# 7_DAC_and_MIC.net
KiCad netlist of a schematic drawn in Altium Designer
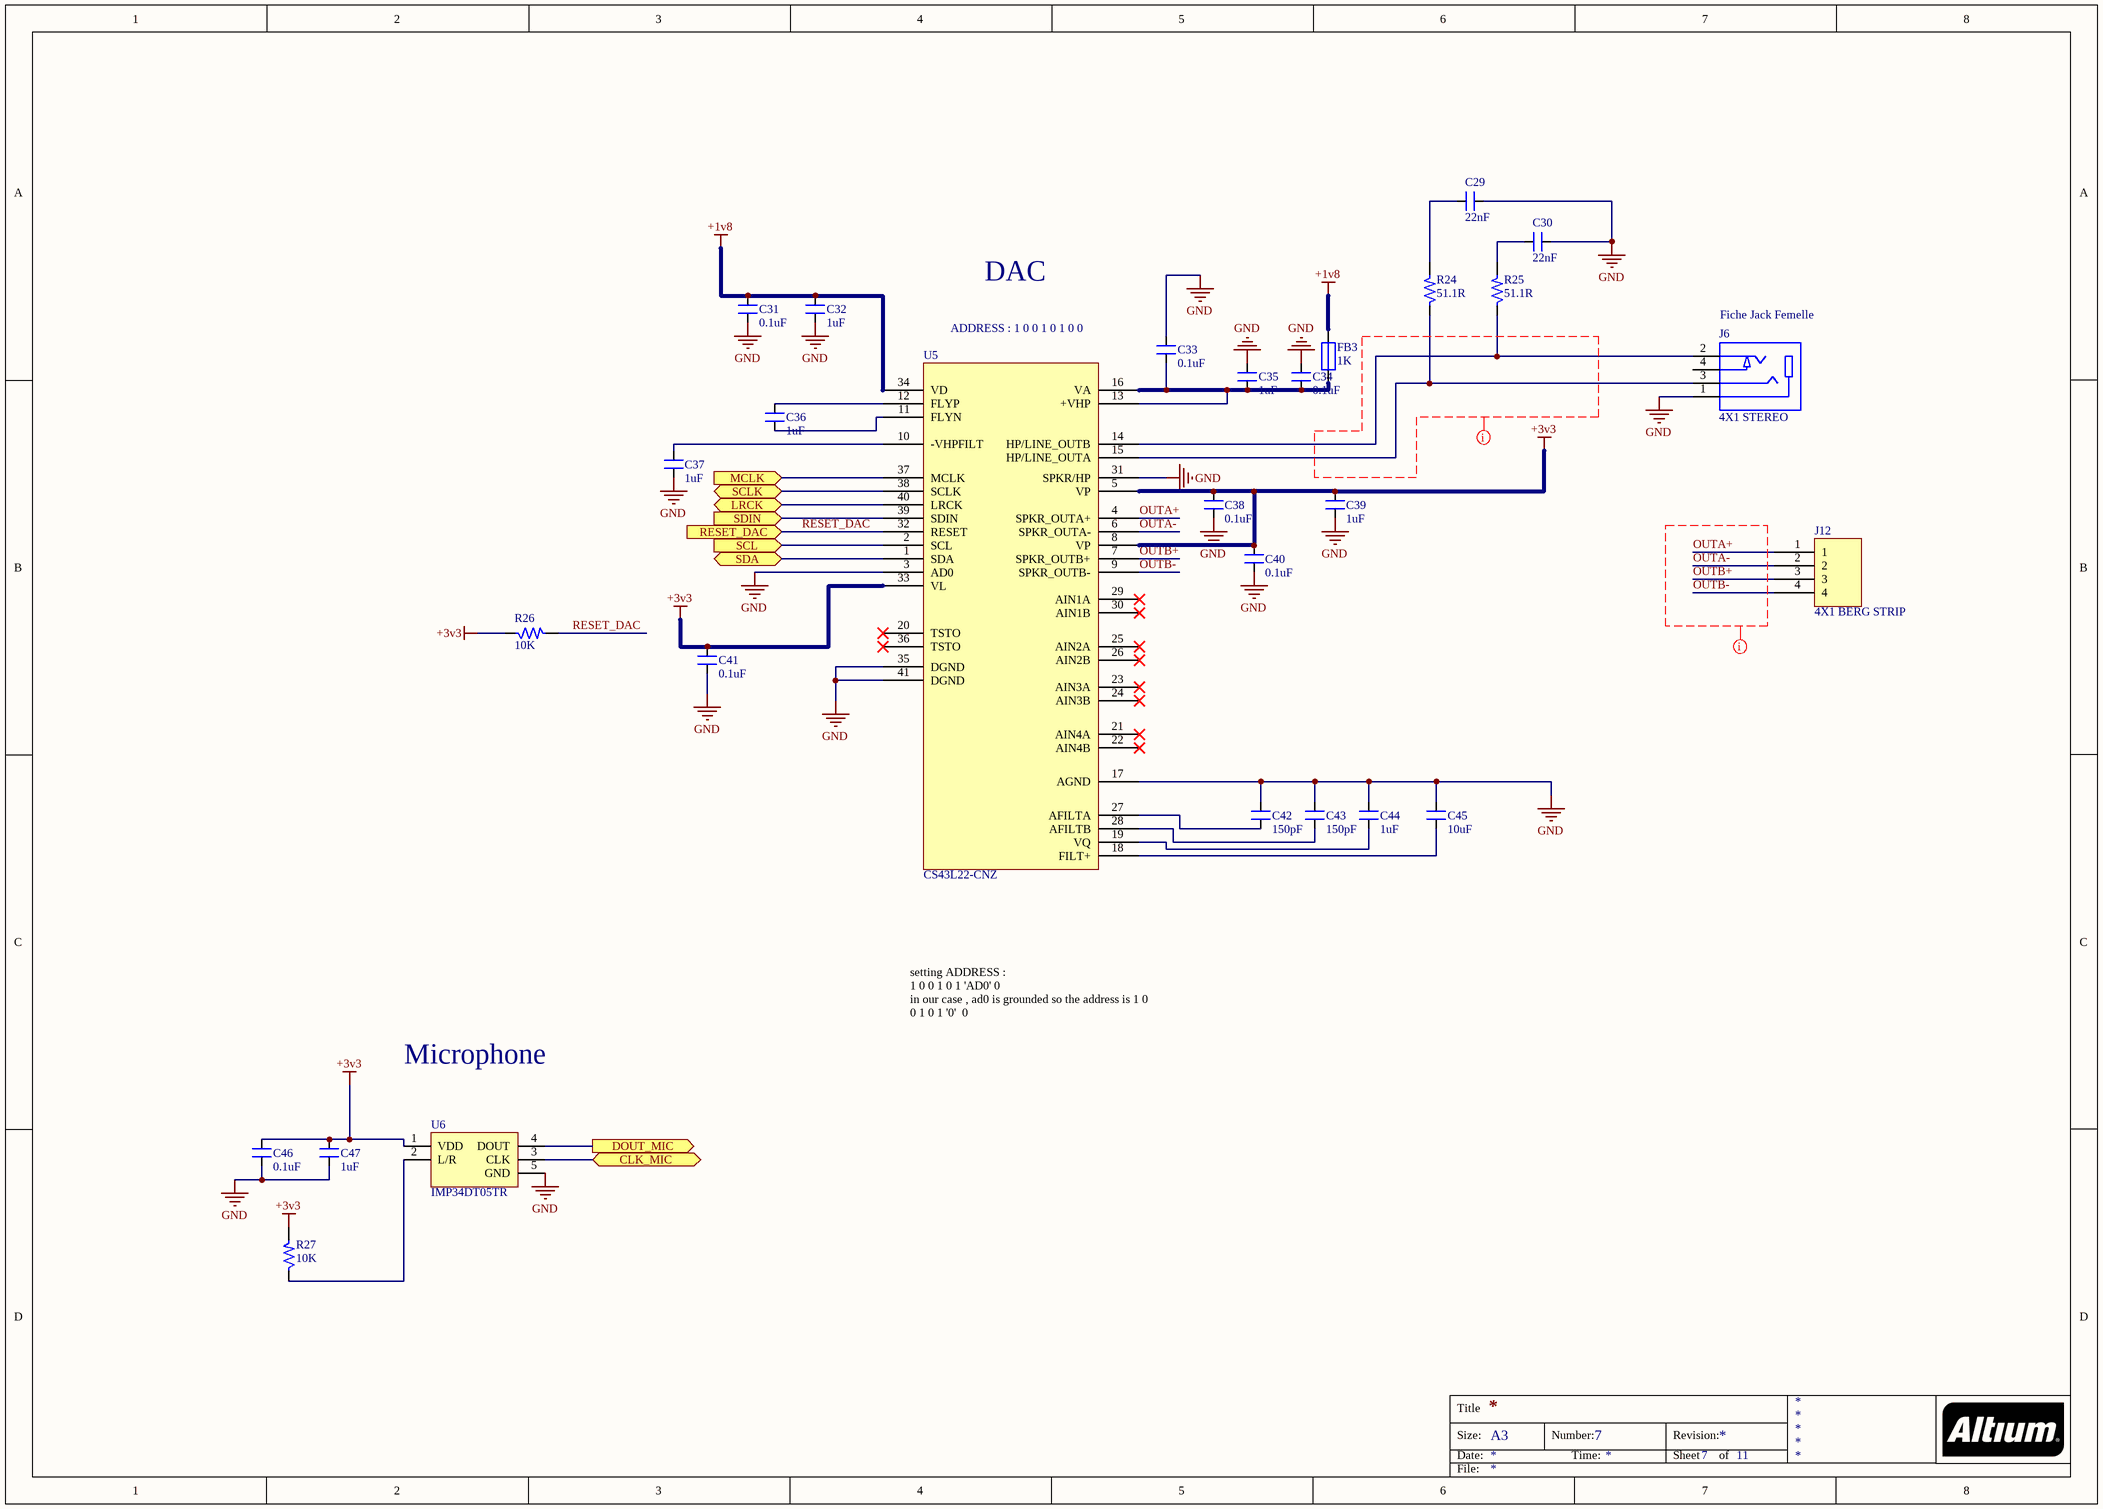
[diagram p0: [7]DAC_and_MIC.SchDoc]

(export (version "E")
  (design (tool "Eeschema 10.0.6"))
  (components
    (comp (ref "C29")
      (value "22nF")
      (footprint "CAP_0805")
      (description "0.022µF ±10% 50V Ceramic Capacitor X7R 0805 (2012 Metric)")
      (fields
        (field (name "MANUFACTURER") "Samsung Electro-Mechanics")
        (field (name "MANUFACTURER PART NUMBER") "CL21B223KBANNNC")
      )
      (libsource (lib "ESTEEMPCBLIB") (part "CAP_22nF-50V-10%-0805"))
    )
    (comp (ref "C30")
      (value "22nF")
      (footprint "CAP_0805")
      (description "0.022µF ±10% 50V Ceramic Capacitor X7R 0805 (2012 Metric)")
      (fields
        (field (name "MANUFACTURER") "Samsung Electro-Mechanics")
        (field (name "MANUFACTURER PART NUMBER") "CL21B223KBANNNC")
      )
      (libsource (lib "ESTEEMPCBLIB") (part "CAP_22nF-50V-10%-0805"))
    )
    (comp (ref "C31")
      (value "0.1uF")
      (footprint "CAP_0805")
      (description "0.1µF ±5% 50V Ceramic Capacitor X7R 0805 (2012 Metric)")
      (fields
        (field (name "MANUFACTURER") "AVX Corporation")
        (field (name "MANUFACTURER PART NUMBER") "08055C104JAT4A")
      )
      (libsource (lib "ESTEEMPCBLIB") (part "CAP_0.1uF-50V-5%-0805"))
    )
    (comp (ref "C32")
      (value "1uF")
      (footprint "CAP_0805")
      (description "1µF ±5% 50V Ceramic Capacitor X7R 0805 (2012 Metric)")
      (fields
        (field (name "MANUFACTURER") "Samsung")
        (field (name "MANUFACTURER PART NUMBER") "CC0805JKX7R9BB105")
      )
      (libsource (lib "ESTEEMPCBLIB") (part "CAP_1uF-50V-5%-0805"))
    )
    (comp (ref "C33")
      (value "0.1uF")
      (footprint "CAP_0805")
      (description "0.1µF ±5% 50V Ceramic Capacitor X7R 0805 (2012 Metric)")
      (fields
        (field (name "MANUFACTURER") "AVX Corporation")
        (field (name "MANUFACTURER PART NUMBER") "08055C104JAT4A")
      )
      (libsource (lib "ESTEEMPCBLIB") (part "CAP_0.1uF-50V-5%-0805"))
    )
    (comp (ref "C34")
      (value "0.1uF")
      (footprint "CAP_0805")
      (description "0.1µF ±5% 50V Ceramic Capacitor X7R 0805 (2012 Metric)")
      (fields
        (field (name "MANUFACTURER") "AVX Corporation")
        (field (name "MANUFACTURER PART NUMBER") "08055C104JAT4A")
      )
      (libsource (lib "ESTEEMPCBLIB") (part "CAP_0.1uF-50V-5%-0805"))
    )
    (comp (ref "C35")
      (value "1uF")
      (footprint "CAP_0805")
      (description "1µF ±5% 50V Ceramic Capacitor X7R 0805 (2012 Metric)")
      (fields
        (field (name "MANUFACTURER") "Samsung")
        (field (name "MANUFACTURER PART NUMBER") "CC0805JKX7R9BB105")
      )
      (libsource (lib "ESTEEMPCBLIB") (part "CAP_1uF-50V-5%-0805"))
    )
    (comp (ref "C36")
      (value "1uF")
      (footprint "CAP_0805")
      (description "1µF ±5% 50V Ceramic Capacitor X7R 0805 (2012 Metric)")
      (fields
        (field (name "MANUFACTURER") "Samsung")
        (field (name "MANUFACTURER PART NUMBER") "CC0805JKX7R9BB105")
      )
      (libsource (lib "ESTEEMPCBLIB") (part "CAP_1uF-50V-5%-0805"))
    )
    (comp (ref "C37")
      (value "1uF")
      (footprint "CAP_0805")
      (description "1µF ±5% 50V Ceramic Capacitor X7R 0805 (2012 Metric)")
      (fields
        (field (name "MANUFACTURER") "Samsung")
        (field (name "MANUFACTURER PART NUMBER") "CC0805JKX7R9BB105")
      )
      (libsource (lib "ESTEEMPCBLIB") (part "CAP_1uF-50V-5%-0805"))
    )
    (comp (ref "C38")
      (value "0.1uF")
      (footprint "CAP_0805")
      (description "0.1µF ±5% 50V Ceramic Capacitor X7R 0805 (2012 Metric)")
      (fields
        (field (name "MANUFACTURER") "AVX Corporation")
        (field (name "MANUFACTURER PART NUMBER") "08055C104JAT4A")
      )
      (libsource (lib "ESTEEMPCBLIB") (part "CAP_0.1uF-50V-5%-0805"))
    )
    (comp (ref "C39")
      (value "1uF")
      (footprint "CAP_0805")
      (description "1µF ±5% 50V Ceramic Capacitor X7R 0805 (2012 Metric)")
      (fields
        (field (name "MANUFACTURER") "Samsung")
        (field (name "MANUFACTURER PART NUMBER") "CC0805JKX7R9BB105")
      )
      (libsource (lib "ESTEEMPCBLIB") (part "CAP_1uF-50V-5%-0805"))
    )
    (comp (ref "C40")
      (value "0.1uF")
      (footprint "CAP_0805")
      (description "0.1µF ±5% 50V Ceramic Capacitor X7R 0805 (2012 Metric)")
      (fields
        (field (name "MANUFACTURER") "AVX Corporation")
        (field (name "MANUFACTURER PART NUMBER") "08055C104JAT4A")
      )
      (libsource (lib "ESTEEMPCBLIB") (part "CAP_0.1uF-50V-5%-0805"))
    )
    (comp (ref "C41")
      (value "0.1uF")
      (footprint "CAP_0805")
      (description "0.1µF ±5% 50V Ceramic Capacitor X7R 0805 (2012 Metric)")
      (fields
        (field (name "MANUFACTURER") "AVX Corporation")
        (field (name "MANUFACTURER PART NUMBER") "08055C104JAT4A")
      )
      (libsource (lib "ESTEEMPCBLIB") (part "CAP_0.1uF-50V-5%-0805"))
    )
    (comp (ref "C42")
      (value "150pF")
      (footprint "CAP_0805")
      (description "150pF ±10% 50V Ceramic Capacitor C0G, NP0 0805 (2012 Metric)")
      (fields
        (field (name "MANUFACTURER") "AVX Corporation")
        (field (name "MANUFACTURER PART NUMBER") "08055A151KAT2A")
      )
      (libsource (lib "ESTEEMPCBLIB") (part "CAP_150pF-50V-10%-0805"))
    )
    (comp (ref "C43")
      (value "150pF")
      (footprint "CAP_0805")
      (description "150pF ±10% 50V Ceramic Capacitor C0G, NP0 0805 (2012 Metric)")
      (fields
        (field (name "MANUFACTURER") "AVX Corporation")
        (field (name "MANUFACTURER PART NUMBER") "08055A151KAT2A")
      )
      (libsource (lib "ESTEEMPCBLIB") (part "CAP_150pF-50V-10%-0805"))
    )
    (comp (ref "C44")
      (value "1uF")
      (footprint "CAP_0805")
      (description "1µF ±5% 50V Ceramic Capacitor X7R 0805 (2012 Metric)")
      (fields
        (field (name "MANUFACTURER") "Samsung")
        (field (name "MANUFACTURER PART NUMBER") "CC0805JKX7R9BB105")
      )
      (libsource (lib "ESTEEMPCBLIB") (part "CAP_1uF-50V-5%-0805"))
    )
    (comp (ref "C45")
      (value "10uF")
      (footprint "CAP_1206")
      (description "10µF ±10% 50V Ceramic Capacitor X7R 1206 (3216 Metric)")
      (fields
        (field (name "MANUFACTURER") "KEMET")
        (field (name "MANUFACTURER PART NUMBER") "CL31B106KBHNNNE")
      )
      (libsource (lib "ESTEEMPCBLIB") (part "CAP_10uF-50V-10%-1206"))
    )
    (comp (ref "C46")
      (value "0.1uF")
      (footprint "CAP_0805")
      (description "0.1µF ±5% 50V Ceramic Capacitor X7R 0805 (2012 Metric)")
      (fields
        (field (name "MANUFACTURER") "AVX Corporation")
        (field (name "MANUFACTURER PART NUMBER") "08055C104JAT4A")
      )
      (libsource (lib "ESTEEMPCBLIB") (part "CAP_0.1uF-50V-5%-0805"))
    )
    (comp (ref "C47")
      (value "1uF")
      (footprint "CAP_0805")
      (description "1µF ±5% 50V Ceramic Capacitor X7R 0805 (2012 Metric)")
      (fields
        (field (name "MANUFACTURER") "Samsung")
        (field (name "MANUFACTURER PART NUMBER") "CC0805JKX7R9BB105")
      )
      (libsource (lib "ESTEEMPCBLIB") (part "CAP_1uF-50V-5%-0805"))
    )
    (comp (ref "FB3")
      (value "1K")
      (footprint "IND_0805")
      (description "1 kOhms @ 100MHz 1 Power Line Ferrite Bead 0805 (2012 Metric) 1.6A")
      (fields
        (field (name "MANUFACTURER") "Laird")
        (field (name "MANUFACTURER PART NUMBER") "BLM21SP102SH1D")
      )
      (libsource (lib "ESTEEMPCBLIB") (part "FB_1K-100MHZ-1.6A-0805"))
    )
    (comp (ref "J6")
      (value "4X1 STEREO")
      (footprint "CON_SJ-2504A-SMT-TR_SMD")
      (fields
        (field (name "MANUFACTURER") "CUI Devices")
        (field (name "MANUFACTURER PART NUMBER") "SJ-2504A-SMT-TR")
      )
      (libsource (lib "ESTEEMPCBLIB") (part "CON-PLG-STEREO_4X1-100-RA-SMD"))
    )
    (comp (ref "J12")
      (value "4X1 BERG STRIP")
      (footprint "CON4_100_40D72_TH_ST_MALE")
      (description "4 Pins, 1 Row 2.54mm Pitch, Straight bergstrip, Male")
      (fields (field (name "MANUFACTURER") "NA"))
      (libsource (lib "ESTEEMPCBLIB") (part "CON-BS-PLG_4X1-100-ST-TH"))
    )
    (comp (ref "R24")
      (value "51.1R")
      (footprint "RES_0603")
      (description "51.1 Ohms ±1% 0.1W, 1/10W Chip Resistor 0603 (1608 Metric) Thick Film")
      (fields
        (field (name "MANUFACTURER") "Vishay Dale")
        (field (name "MANUFACTURER PART NUMBER") "CRCW060351R1FKEAC")
      )
      (libsource (lib "ESTEEMPCBLIB") (part "RES_51.1R-0.1W-1%-0603"))
    )
    (comp (ref "R25")
      (value "51.1R")
      (footprint "RES_0603")
      (description "51.1 Ohms ±1% 0.1W, 1/10W Chip Resistor 0603 (1608 Metric) Thick Film")
      (fields
        (field (name "MANUFACTURER") "Vishay Dale")
        (field (name "MANUFACTURER PART NUMBER") "CRCW060351R1FKEAC")
      )
      (libsource (lib "ESTEEMPCBLIB") (part "RES_51.1R-0.1W-1%-0603"))
    )
    (comp (ref "R26")
      (value "10K")
      (footprint "RES_0603")
      (description "10 kOhms ±1% 0.1W, 1/10W Chip Resistor 0603 (1608 Metric) Automotive AEC-Q200 Thick Film")
      (fields (field (name "MANUFACTURER") "Walsin") (field (name "MANUFACTURER PART NUMBER") "WR06X1002FTL"))
      (libsource (lib "ESTEEMPCBLIB") (part "RES_10K-0.1W-1%-0603"))
    )
    (comp (ref "R27")
      (value "10K")
      (footprint "RES_0603")
      (description "10 kOhms ±1% 0.1W, 1/10W Chip Resistor 0603 (1608 Metric) Automotive AEC-Q200 Thick Film")
      (fields (field (name "MANUFACTURER") "Walsin") (field (name "MANUFACTURER PART NUMBER") "WR06X1002FTL"))
      (libsource (lib "ESTEEMPCBLIB") (part "RES_10K-0.1W-1%-0603"))
    )
    (comp (ref "U5")
      (value "CS43L22-CNZ")
      (footprint "QFN40_19_284_33X9_SMD")
      (description "Audio D/A Converter ICs Low Power Stereo DAC w/ClassD Spkr Driver")
      (fields (field (name "MANUFACTURER") "Cirrus Logic"))
      (libsource (lib "ESTEEMPCBLIB") (part "IC_CS43L22"))
    )
    (comp (ref "U6")
      (value "IMP34DT05TR")
      (footprint "HCLGA-4_53_137_15X37_SMD")
      (description "MEMS Microphones AUTO & INDUSTRIAL SENSORS")
      (fields (field (name "MANUFACTURER") "STMicroelectronics"))
      (libsource (lib "ESTEEMPCBLIB") (part "IC_IMP34DT05TR"))
    )
  )
  (nets
    (net (code "1") (name "+1v8") (class "Default")
      (node (ref "C31") (pin "2") (pinfunction "2_2") (pintype "passive"))
      (node (ref "C32") (pin "2") (pinfunction "2_2") (pintype "passive"))
      (node (ref "FB3") (pin "2") (pinfunction "2_2") (pintype "passive"))
      (node (ref "U5") (pin "34") (pinfunction "VD_34") (pintype "passive"))
    )
    (net (code "2") (name "+3v3") (class "Default")
      (node (ref "C38") (pin "2") (pinfunction "2_2") (pintype "passive"))
      (node (ref "C39") (pin "2") (pinfunction "2_2") (pintype "passive"))
      (node (ref "C40") (pin "2") (pinfunction "2_2") (pintype "passive"))
      (node (ref "C41") (pin "2") (pinfunction "2_2") (pintype "passive"))
      (node (ref "C46") (pin "2") (pinfunction "2_2") (pintype "passive"))
      (node (ref "C47") (pin "2") (pinfunction "2_2") (pintype "passive"))
      (node (ref "R26") (pin "1") (pinfunction "1_1") (pintype "passive"))
      (node (ref "R27") (pin "2") (pinfunction "2_2") (pintype "passive"))
      (node (ref "U5") (pin "33") (pinfunction "VL_33") (pintype "passive"))
      (node (ref "U5") (pin "5") (pinfunction "VP_5") (pintype "passive"))
      (node (ref "U5") (pin "8") (pinfunction "VP_8") (pintype "passive"))
      (node (ref "U6") (pin "1") (pinfunction "VDD_1") (pintype "passive"))
    )
    (net (code "3") (name "/CLK_MIC") (class "Default")
      (node (ref "U6") (pin "3") (pinfunction "CLK_3") (pintype "passive"))
    )
    (net (code "4") (name "/DOUT_MIC") (class "Default")
      (node (ref "U6") (pin "4") (pinfunction "DOUT_4") (pintype "passive"))
    )
    (net (code "5") (name "/LRCK") (class "Default")
      (node (ref "U5") (pin "40") (pinfunction "LRCK_40") (pintype "passive"))
    )
    (net (code "6") (name "/MCLK") (class "Default")
      (node (ref "U5") (pin "37") (pinfunction "MCLK_37") (pintype "passive"))
    )
    (net (code "7") (name "/OUTA+") (class "Default")
      (node (ref "J12") (pin "1") (pinfunction "1_1") (pintype "passive"))
      (node (ref "U5") (pin "4") (pinfunction "SPKR_OUTA+_4") (pintype "passive"))
    )
    (net (code "8") (name "/OUTA-") (class "Default")
      (node (ref "J12") (pin "2") (pinfunction "2_2") (pintype "passive"))
      (node (ref "U5") (pin "6") (pinfunction "SPKR_OUTA-_6") (pintype "passive"))
    )
    (net (code "9") (name "/OUTB+") (class "Default")
      (node (ref "J12") (pin "3") (pinfunction "3_3") (pintype "passive"))
      (node (ref "U5") (pin "7") (pinfunction "SPKR_OUTB+_7") (pintype "passive"))
    )
    (net (code "10") (name "/OUTB-") (class "Default")
      (node (ref "J12") (pin "4") (pinfunction "4_4") (pintype "passive"))
      (node (ref "U5") (pin "9") (pinfunction "SPKR_OUTB-_9") (pintype "passive"))
    )
    (net (code "11") (name "/RESET_DAC") (class "Default")
      (node (ref "R26") (pin "2") (pinfunction "2_2") (pintype "passive"))
      (node (ref "U5") (pin "32") (pinfunction "RESET_32") (pintype "passive"))
    )
    (net (code "12") (name "/SCL") (class "Default")
      (node (ref "U5") (pin "2") (pinfunction "SCL_2") (pintype "passive"))
    )
    (net (code "13") (name "/SCLK") (class "Default")
      (node (ref "U5") (pin "38") (pinfunction "SCLK_38") (pintype "passive"))
    )
    (net (code "14") (name "/SDA") (class "Default")
      (node (ref "U5") (pin "1") (pinfunction "SDA_1") (pintype "passive"))
    )
    (net (code "15") (name "/SDIN") (class "Default")
      (node (ref "U5") (pin "39") (pinfunction "SDIN_39") (pintype "passive"))
    )
    (net (code "16") (name "GND") (class "Default")
      (node (ref "C29") (pin "2") (pinfunction "2_2") (pintype "passive"))
      (node (ref "C30") (pin "2") (pinfunction "2_2") (pintype "passive"))
      (node (ref "C31") (pin "1") (pinfunction "1_1") (pintype "passive"))
      (node (ref "C32") (pin "1") (pinfunction "1_1") (pintype "passive"))
      (node (ref "C33") (pin "2") (pinfunction "2_2") (pintype "passive"))
      (node (ref "C34") (pin "1") (pinfunction "1_1") (pintype "passive"))
      (node (ref "C35") (pin "1") (pinfunction "1_1") (pintype "passive"))
      (node (ref "C37") (pin "1") (pinfunction "1_1") (pintype "passive"))
      (node (ref "C38") (pin "1") (pinfunction "1_1") (pintype "passive"))
      (node (ref "C39") (pin "1") (pinfunction "1_1") (pintype "passive"))
      (node (ref "C40") (pin "1") (pinfunction "1_1") (pintype "passive"))
      (node (ref "C41") (pin "1") (pinfunction "1_1") (pintype "passive"))
      (node (ref "C42") (pin "2") (pinfunction "2_2") (pintype "passive"))
      (node (ref "C43") (pin "2") (pinfunction "2_2") (pintype "passive"))
      (node (ref "C44") (pin "2") (pinfunction "2_2") (pintype "passive"))
      (node (ref "C45") (pin "2") (pinfunction "2_2") (pintype "passive"))
      (node (ref "C46") (pin "1") (pinfunction "1_1") (pintype "passive"))
      (node (ref "C47") (pin "1") (pinfunction "1_1") (pintype "passive"))
      (node (ref "J6") (pin "1") (pinfunction "1_1") (pintype "passive"))
      (node (ref "U5") (pin "17") (pinfunction "AGND_17") (pintype "passive"))
      (node (ref "U5") (pin "3") (pinfunction "AD0_3") (pintype "passive"))
      (node (ref "U5") (pin "31") (pinfunction "SPKR/HP_31") (pintype "passive"))
      (node (ref "U5") (pin "35") (pinfunction "DGND_35") (pintype "passive"))
      (node (ref "U5") (pin "41") (pinfunction "DGND_41") (pintype "passive"))
      (node (ref "U6") (pin "5") (pinfunction "GND_5") (pintype "passive"))
    )
    (net (code "17") (name "Net-(C29-Pad1)") (class "Default")
      (node (ref "C29") (pin "1") (pinfunction "1_1") (pintype "passive"))
      (node (ref "R24") (pin "2") (pinfunction "2_2") (pintype "passive"))
    )
    (net (code "18") (name "Net-(C30-Pad1)") (class "Default")
      (node (ref "C30") (pin "1") (pinfunction "1_1") (pintype "passive"))
      (node (ref "R25") (pin "2") (pinfunction "2_2") (pintype "passive"))
    )
    (net (code "19") (name "Net-(U5-+VHP)") (class "Default")
      (node (ref "C33") (pin "1") (pinfunction "1_1") (pintype "passive"))
      (node (ref "C34") (pin "2") (pinfunction "2_2") (pintype "passive"))
      (node (ref "C35") (pin "2") (pinfunction "2_2") (pintype "passive"))
      (node (ref "FB3") (pin "1") (pinfunction "1_1") (pintype "passive"))
      (node (ref "U5") (pin "13") (pinfunction "+VHP_13") (pintype "passive"))
      (node (ref "U5") (pin "16") (pinfunction "VA_16") (pintype "passive"))
    )
    (net (code "20") (name "Net-(U5--VHPFILT)") (class "Default")
      (node (ref "C37") (pin "2") (pinfunction "2_2") (pintype "passive"))
      (node (ref "U5") (pin "10") (pinfunction "-VHPFILT_10") (pintype "passive"))
    )
    (net (code "21") (name "Net-(U5-AFILTA)") (class "Default")
      (node (ref "C42") (pin "1") (pinfunction "1_1") (pintype "passive"))
      (node (ref "U5") (pin "27") (pinfunction "AFILTA_27") (pintype "passive"))
    )
    (net (code "22") (name "Net-(U5-AFILTB)") (class "Default")
      (node (ref "C43") (pin "1") (pinfunction "1_1") (pintype "passive"))
      (node (ref "U5") (pin "28") (pinfunction "AFILTB_28") (pintype "passive"))
    )
    (net (code "23") (name "Net-(U5-FILT+)") (class "Default")
      (node (ref "C45") (pin "1") (pinfunction "1_1") (pintype "passive"))
      (node (ref "U5") (pin "18") (pinfunction "FILT+_18") (pintype "passive"))
    )
    (net (code "24") (name "Net-(U5-FLYN)") (class "Default")
      (node (ref "C36") (pin "1") (pinfunction "1_1") (pintype "passive"))
      (node (ref "U5") (pin "11") (pinfunction "FLYN_11") (pintype "passive"))
    )
    (net (code "25") (name "Net-(U5-FLYP)") (class "Default")
      (node (ref "C36") (pin "2") (pinfunction "2_2") (pintype "passive"))
      (node (ref "U5") (pin "12") (pinfunction "FLYP_12") (pintype "passive"))
    )
    (net (code "26") (name "Net-(U5-HP{slash}LINE_OUTA)") (class "Default")
      (node (ref "J6") (pin "3") (pinfunction "3_3") (pintype "passive"))
      (node (ref "R24") (pin "1") (pinfunction "1_1") (pintype "passive"))
      (node (ref "U5") (pin "15") (pinfunction "HP/LINE_OUTA_15") (pintype "passive"))
    )
    (net (code "27") (name "Net-(U5-HP{slash}LINE_OUTB)") (class "Default")
      (node (ref "J6") (pin "2") (pinfunction "2_2") (pintype "passive"))
      (node (ref "R25") (pin "1") (pinfunction "1_1") (pintype "passive"))
      (node (ref "U5") (pin "14") (pinfunction "HP/LINE_OUTB_14") (pintype "passive"))
    )
    (net (code "28") (name "Net-(U5-VQ)") (class "Default")
      (node (ref "C44") (pin "1") (pinfunction "1_1") (pintype "passive"))
      (node (ref "U5") (pin "19") (pinfunction "VQ_19") (pintype "passive"))
    )
    (net (code "29") (name "Net-(U6-L{slash}R)") (class "Default")
      (node (ref "R27") (pin "1") (pinfunction "1_1") (pintype "passive"))
      (node (ref "U6") (pin "2") (pinfunction "L/R_2") (pintype "passive"))
    )
    (net (code "30") (name "unconnected-(J6-Pad4)") (class "Default")
      (node (ref "J6") (pin "4") (pinfunction "4_4") (pintype "passive"))
    )
    (net (code "31") (name "unconnected-(U5-AIN1A-Pad29)") (class "Default")
      (node (ref "U5") (pin "29") (pinfunction "AIN1A_29") (pintype "passive+no_connect"))
    )
    (net (code "32") (name "unconnected-(U5-AIN1B-Pad30)") (class "Default")
      (node (ref "U5") (pin "30") (pinfunction "AIN1B_30") (pintype "passive+no_connect"))
    )
    (net (code "33") (name "unconnected-(U5-AIN2A-Pad25)") (class "Default")
      (node (ref "U5") (pin "25") (pinfunction "AIN2A_25") (pintype "passive+no_connect"))
    )
    (net (code "34") (name "unconnected-(U5-AIN2B-Pad26)") (class "Default")
      (node (ref "U5") (pin "26") (pinfunction "AIN2B_26") (pintype "passive+no_connect"))
    )
    (net (code "35") (name "unconnected-(U5-AIN3A-Pad23)") (class "Default")
      (node (ref "U5") (pin "23") (pinfunction "AIN3A_23") (pintype "passive+no_connect"))
    )
    (net (code "36") (name "unconnected-(U5-AIN3B-Pad24)") (class "Default")
      (node (ref "U5") (pin "24") (pinfunction "AIN3B_24") (pintype "passive+no_connect"))
    )
    (net (code "37") (name "unconnected-(U5-AIN4A-Pad21)") (class "Default")
      (node (ref "U5") (pin "21") (pinfunction "AIN4A_21") (pintype "passive+no_connect"))
    )
    (net (code "38") (name "unconnected-(U5-AIN4B-Pad22)") (class "Default")
      (node (ref "U5") (pin "22") (pinfunction "AIN4B_22") (pintype "passive+no_connect"))
    )
    (net (code "39") (name "unconnected-(U5-TSTO-Pad20)") (class "Default")
      (node (ref "U5") (pin "20") (pinfunction "TSTO_20") (pintype "passive+no_connect"))
    )
    (net (code "40") (name "unconnected-(U5-TSTO-Pad36)") (class "Default")
      (node (ref "U5") (pin "36") (pinfunction "TSTO_36") (pintype "passive+no_connect"))
    )
  )
)
